# GMSL_SERIALIZER.net
KiCad netlist of a schematic drawn in Altium Designer
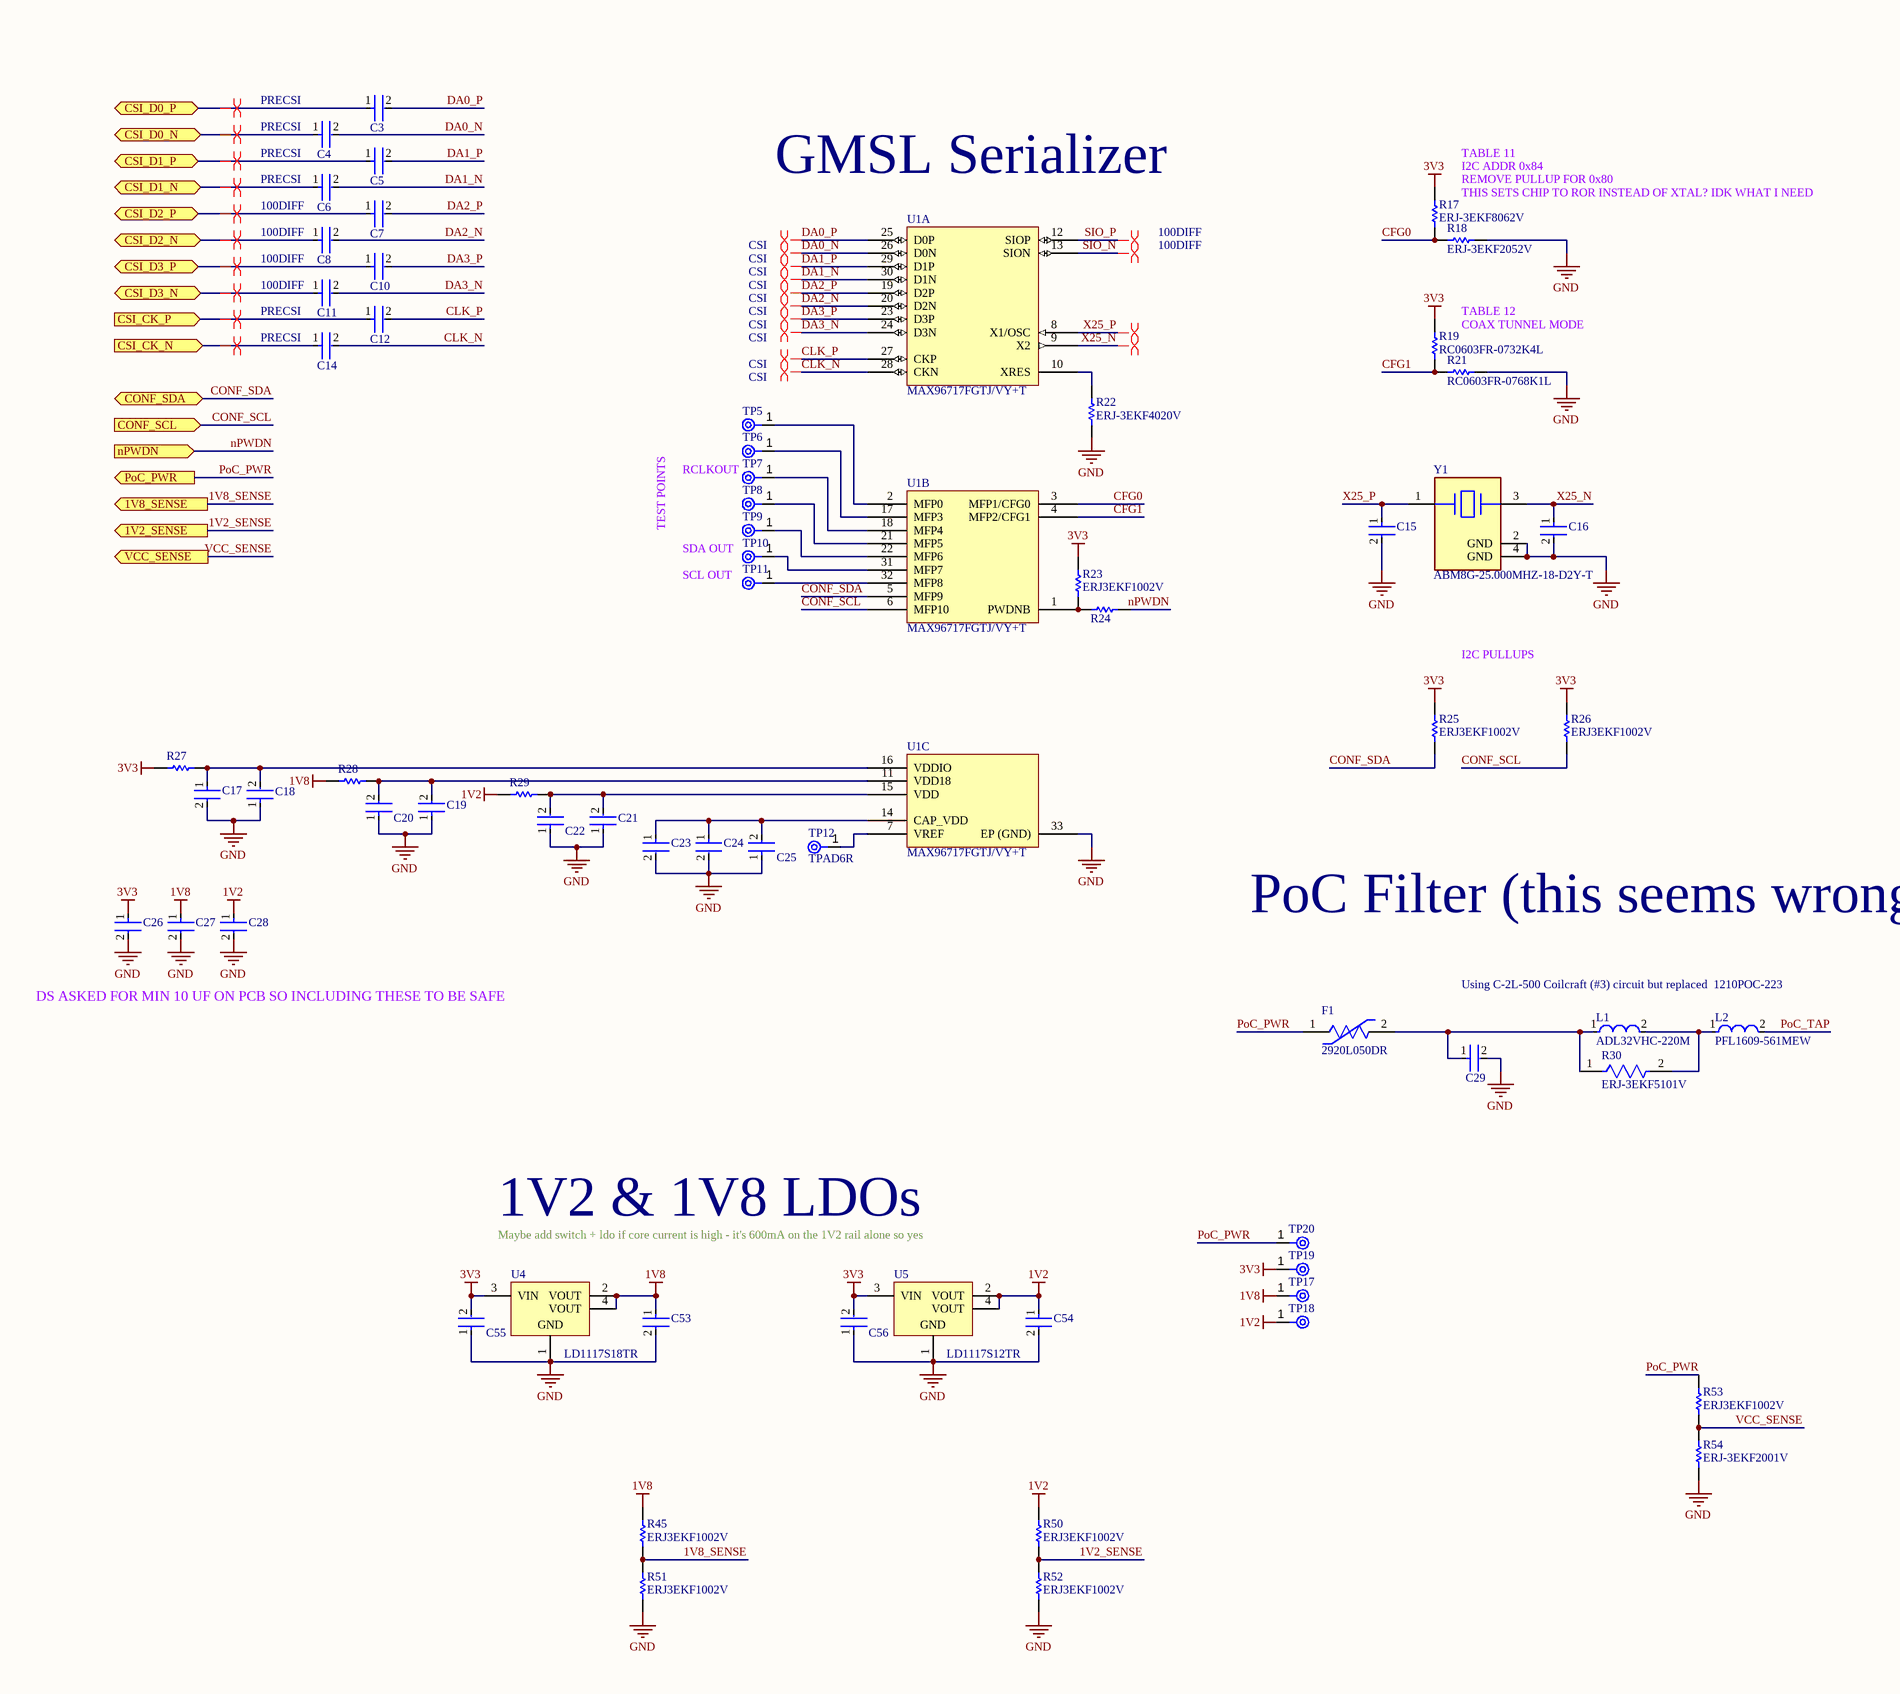
[diagram p0: GMSL_SERIALIZER.SchDoc, left]
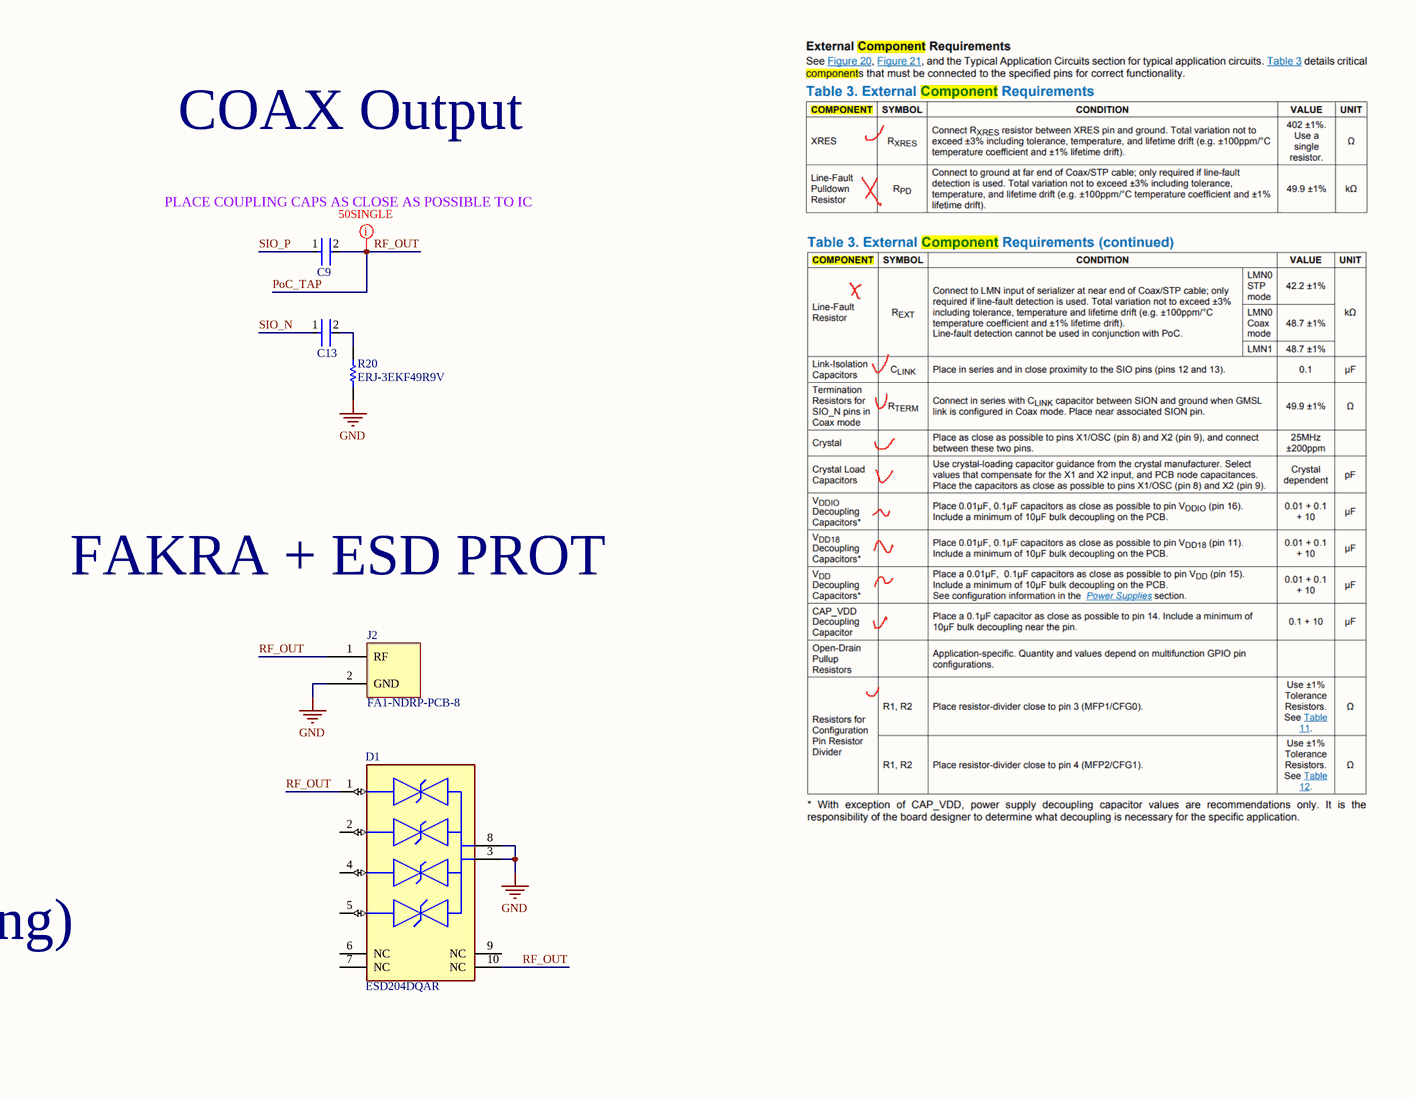
[diagram p1: GMSL_SERIALIZER.SchDoc, right]

(export (version "E")
  (design (tool "Eeschema 10.0.6"))
  (components
    (comp (ref "C3")
      (value "C1005X7R1H104K050BB")
      (footprint "FP-C1005-050-0_05-IPC_C")
      (description "Multilayer Ceramic Capacitors 100nF ±10% 50V X7R SMD 0402")
      (fields (field (name "VOLTAGE") "50V") (field (name "TOLERANCE") "10%"))
      (libsource (lib "Altium Content Vault") (part "b4654b650e69147ec39a6b967a45e02"))
    )
    (comp (ref "C4")
      (value "C1005X7R1H104K050BB")
      (footprint "FP-C1005-050-0_05-IPC_C")
      (description "Multilayer Ceramic Capacitors 100nF ±10% 50V X7R SMD 0402")
      (fields (field (name "VOLTAGE") "50V") (field (name "TOLERANCE") "10%"))
      (libsource (lib "Altium Content Vault") (part "b4654b650e69147ec39a6b967a45e02"))
    )
    (comp (ref "C5")
      (value "C1005X7R1H104K050BB")
      (footprint "FP-C1005-050-0_05-IPC_C")
      (description "Multilayer Ceramic Capacitors 100nF ±10% 50V X7R SMD 0402")
      (fields (field (name "VOLTAGE") "50V") (field (name "TOLERANCE") "10%"))
      (libsource (lib "Altium Content Vault") (part "b4654b650e69147ec39a6b967a45e02"))
    )
    (comp (ref "C6")
      (value "C1005X7R1H104K050BB")
      (footprint "FP-C1005-050-0_05-IPC_C")
      (description "Multilayer Ceramic Capacitors 100nF ±10% 50V X7R SMD 0402")
      (fields (field (name "VOLTAGE") "50V") (field (name "TOLERANCE") "10%"))
      (libsource (lib "Altium Content Vault") (part "b4654b650e69147ec39a6b967a45e02"))
    )
    (comp (ref "C7")
      (value "C1005X7R1H104K050BB")
      (footprint "FP-C1005-050-0_05-IPC_C")
      (description "Multilayer Ceramic Capacitors 100nF ±10% 50V X7R SMD 0402")
      (fields (field (name "VOLTAGE") "50V") (field (name "TOLERANCE") "10%"))
      (libsource (lib "Altium Content Vault") (part "b4654b650e69147ec39a6b967a45e02"))
    )
    (comp (ref "C8")
      (value "C1005X7R1H104K050BB")
      (footprint "FP-C1005-050-0_05-IPC_C")
      (description "Multilayer Ceramic Capacitors 100nF ±10% 50V X7R SMD 0402")
      (fields (field (name "VOLTAGE") "50V") (field (name "TOLERANCE") "10%"))
      (libsource (lib "Altium Content Vault") (part "b4654b650e69147ec39a6b967a45e02"))
    )
    (comp (ref "C9")
      (value "C1005X7R1H104K050BB")
      (footprint "FP-C1005-050-0_05-IPC_C")
      (description "Multilayer Ceramic Capacitors 100nF ±10% 50V X7R SMD 0402")
      (fields (field (name "VOLTAGE") "50V") (field (name "TOLERANCE") "10%"))
      (libsource (lib "Altium Content Vault") (part "b4654b650e69147ec39a6b967a45e02"))
    )
    (comp (ref "C10")
      (value "C1005X7R1H104K050BB")
      (footprint "FP-C1005-050-0_05-IPC_C")
      (description "Multilayer Ceramic Capacitors 100nF ±10% 50V X7R SMD 0402")
      (fields (field (name "VOLTAGE") "50V") (field (name "TOLERANCE") "10%"))
      (libsource (lib "Altium Content Vault") (part "b4654b650e69147ec39a6b967a45e02"))
    )
    (comp (ref "C11")
      (value "C1005X7R1H104K050BB")
      (footprint "FP-C1005-050-0_05-IPC_C")
      (description "Multilayer Ceramic Capacitors 100nF ±10% 50V X7R SMD 0402")
      (fields (field (name "VOLTAGE") "50V") (field (name "TOLERANCE") "10%"))
      (libsource (lib "Altium Content Vault") (part "b4654b650e69147ec39a6b967a45e02"))
    )
    (comp (ref "C12")
      (value "C1005X7R1H104K050BB")
      (footprint "FP-C1005-050-0_05-IPC_C")
      (description "Multilayer Ceramic Capacitors 100nF ±10% 50V X7R SMD 0402")
      (fields (field (name "VOLTAGE") "50V") (field (name "TOLERANCE") "10%"))
      (libsource (lib "Altium Content Vault") (part "b4654b650e69147ec39a6b967a45e02"))
    )
    (comp (ref "C13")
      (value "C1005X7R1H104K050BB")
      (footprint "FP-C1005-050-0_05-IPC_C")
      (description "Multilayer Ceramic Capacitors 100nF ±10% 50V X7R SMD 0402")
      (fields (field (name "VOLTAGE") "50V") (field (name "TOLERANCE") "10%"))
      (libsource (lib "Altium Content Vault") (part "b4654b650e69147ec39a6b967a45e02"))
    )
    (comp (ref "C14")
      (value "C1005X7R1H104K050BB")
      (footprint "FP-C1005-050-0_05-IPC_C")
      (description "Multilayer Ceramic Capacitors 100nF ±10% 50V X7R SMD 0402")
      (fields (field (name "VOLTAGE") "50V") (field (name "TOLERANCE") "10%"))
      (libsource (lib "Altium Content Vault") (part "b4654b650e69147ec39a6b967a45e02"))
    )
    (comp (ref "C15")
      (value "C0603C300J5GACTU")
      (footprint "FP-C0603C-CF-MFG")
      (description "CAP CER 30PF 50V 5% NP0 0603")
      (fields
        (field (name "MANUFACTURER") "KEMET")
        (field (name "OCTOPART") "https://octopart.com/c0603c300j5gactu-kemet-199455")
      )
      (libsource (lib "Altium Content Vault") (part "b4654b650e69147ec39a6b967a45e02"))
    )
    (comp (ref "C16")
      (value "C0603C300J5GACTU")
      (footprint "FP-C0603C-CF-MFG")
      (description "CAP CER 30PF 50V 5% NP0 0603")
      (fields
        (field (name "MANUFACTURER") "KEMET")
        (field (name "OCTOPART") "https://octopart.com/c0603c300j5gactu-kemet-199455")
      )
      (libsource (lib "Altium Content Vault") (part "b4654b650e69147ec39a6b967a45e02"))
    )
    (comp (ref "C17")
      (value "CL05A106MP5NUNC")
      (footprint "FP-CL05A106MP5NUNC-MFG")
      (description "CAP CER 10UF 10V X5R 0402")
      (fields
        (field (name "OCTOPART") "https://octopart.com/cl05a106mp5nunc-samsung-22457395")
        (field (name "TOLERANCE") "20%")
      )
      (libsource (lib "Altium Content Vault") (part "b4654b650e69147ec39a6b967a45e02"))
    )
    (comp (ref "C18")
      (value "C0402C103M5RACTU")
      (footprint "FP-C0402-BB-MFG")
      (description "CAP CER 10000PF 50V 20% X7R 0402")
      (fields
        (field (name "TOLERANCE") "0.2")
        (field (name "OCTOPART") "https://octopart.com/c0402c103m5ractu-kemet-17125571")
      )
      (libsource (lib "Altium Content Vault") (part "b4654b650e69147ec39a6b967a45e02"))
    )
    (comp (ref "C19")
      (value "C0402C103M5RACTU")
      (footprint "FP-C0402-BB-MFG")
      (description "CAP CER 10000PF 50V 20% X7R 0402")
      (fields
        (field (name "TOLERANCE") "0.2")
        (field (name "OCTOPART") "https://octopart.com/c0402c103m5ractu-kemet-17125571")
      )
      (libsource (lib "Altium Content Vault") (part "b4654b650e69147ec39a6b967a45e02"))
    )
    (comp (ref "C20")
      (value "C1005X7R1H104K050BB")
      (footprint "FP-C1005-050-0_05-IPC_C")
      (description "Multilayer Ceramic Capacitors 100nF ±10% 50V X7R SMD 0402")
      (fields (field (name "VOLTAGE") "50V") (field (name "TOLERANCE") "10%"))
      (libsource (lib "Altium Content Vault") (part "b4654b650e69147ec39a6b967a45e02"))
    )
    (comp (ref "C21")
      (value "C0402C103M5RACTU")
      (footprint "FP-C0402-BB-MFG")
      (description "CAP CER 10000PF 50V 20% X7R 0402")
      (fields
        (field (name "TOLERANCE") "0.2")
        (field (name "OCTOPART") "https://octopart.com/c0402c103m5ractu-kemet-17125571")
      )
      (libsource (lib "Altium Content Vault") (part "b4654b650e69147ec39a6b967a45e02"))
    )
    (comp (ref "C22")
      (value "C1005X7R1H104K050BB")
      (footprint "FP-C1005-050-0_05-IPC_C")
      (description "Multilayer Ceramic Capacitors 100nF ±10% 50V X7R SMD 0402")
      (fields (field (name "VOLTAGE") "50V") (field (name "TOLERANCE") "10%"))
      (libsource (lib "Altium Content Vault") (part "b4654b650e69147ec39a6b967a45e02"))
    )
    (comp (ref "C23")
      (value "CL05A106MP5NUNC")
      (footprint "FP-CL05A106MP5NUNC-MFG")
      (description "CAP CER 10UF 10V X5R 0402")
      (fields
        (field (name "OCTOPART") "https://octopart.com/cl05a106mp5nunc-samsung-22457395")
        (field (name "TOLERANCE") "20%")
      )
      (libsource (lib "Altium Content Vault") (part "b4654b650e69147ec39a6b967a45e02"))
    )
    (comp (ref "C24")
      (value "CL05A106MP5NUNC")
      (footprint "FP-CL05A106MP5NUNC-MFG")
      (description "CAP CER 10UF 10V X5R 0402")
      (fields
        (field (name "OCTOPART") "https://octopart.com/cl05a106mp5nunc-samsung-22457395")
        (field (name "TOLERANCE") "20%")
      )
      (libsource (lib "Altium Content Vault") (part "b4654b650e69147ec39a6b967a45e02"))
    )
    (comp (ref "C25")
      (value "C1005X7R1H104K050BB")
      (footprint "FP-C1005-050-0_05-IPC_C")
      (description "Multilayer Ceramic Capacitors 100nF ±10% 50V X7R SMD 0402")
      (fields (field (name "VOLTAGE") "50V") (field (name "TOLERANCE") "10%"))
      (libsource (lib "Altium Content Vault") (part "b4654b650e69147ec39a6b967a45e02"))
    )
    (comp (ref "C26")
      (value "CL05A106MP5NUNC")
      (footprint "FP-CL05A106MP5NUNC-MFG")
      (description "CAP CER 10UF 10V X5R 0402")
      (fields
        (field (name "OCTOPART") "https://octopart.com/cl05a106mp5nunc-samsung-22457395")
        (field (name "TOLERANCE") "20%")
      )
      (libsource (lib "Altium Content Vault") (part "b4654b650e69147ec39a6b967a45e02"))
    )
    (comp (ref "C27")
      (value "CL05A106MP5NUNC")
      (footprint "FP-CL05A106MP5NUNC-MFG")
      (description "CAP CER 10UF 10V X5R 0402")
      (fields
        (field (name "OCTOPART") "https://octopart.com/cl05a106mp5nunc-samsung-22457395")
        (field (name "TOLERANCE") "20%")
      )
      (libsource (lib "Altium Content Vault") (part "b4654b650e69147ec39a6b967a45e02"))
    )
    (comp (ref "C28")
      (value "CL05A106MP5NUNC")
      (footprint "FP-CL05A106MP5NUNC-MFG")
      (description "CAP CER 10UF 10V X5R 0402")
      (fields
        (field (name "OCTOPART") "https://octopart.com/cl05a106mp5nunc-samsung-22457395")
        (field (name "TOLERANCE") "20%")
      )
      (libsource (lib "Altium Content Vault") (part "b4654b650e69147ec39a6b967a45e02"))
    )
    (comp (ref "C29")
      (value "GRM21BR61E226ME44L")
      (footprint "FP-GRM21B-0_2-e0_2_0_7-IPC_B")
      (description "Chip Multilayer Ceramic Capacitors for General Purpose, 0805, 22uF, X5R, 15%, 20%, 25V")
      (fields (field (name "TOLERANCE") "20%") (field (name "VOLTAGE") "25V"))
      (libsource (lib "Altium Content Vault") (part "b4654b650e69147ec39a6b967a45e02"))
    )
    (comp (ref "C53")
      (value "GRM188R60J106ME47D")
      (footprint "FP-GRM188-0_1-e0_2_0_55-IPC_A")
      (description "Chip Multilayer Ceramic Capacitors for General Purpose, 0603, 10uF, X5R, 15%, 20%, 6.3V")
      (fields (field (name "VOLTAGE") "6.3V") (field (name "TOLERANCE") "20%"))
      (libsource (lib "Altium Content Vault") (part "02cd4be3c70576c341d710602a673aa"))
    )
    (comp (ref "C54")
      (value "GRM188R60J106ME47D")
      (footprint "FP-GRM188-0_1-e0_2_0_55-IPC_A")
      (description "Chip Multilayer Ceramic Capacitors for General Purpose, 0603, 10uF, X5R, 15%, 20%, 6.3V")
      (fields (field (name "VOLTAGE") "6.3V") (field (name "TOLERANCE") "20%"))
      (libsource (lib "Altium Content Vault") (part "02cd4be3c70576c341d710602a673aa"))
    )
    (comp (ref "C55")
      (value "C1005X7R1H104K050BB")
      (footprint "FP-C1005-050-0_05-IPC_C")
      (description "Multilayer Ceramic Capacitors 100nF ±10% 50V X7R SMD 0402")
      (fields (field (name "VOLTAGE") "50V") (field (name "TOLERANCE") "10%"))
      (libsource (lib "Altium Content Vault") (part "b4654b650e69147ec39a6b967a45e02"))
    )
    (comp (ref "C56")
      (value "C1005X7R1H104K050BB")
      (footprint "FP-C1005-050-0_05-IPC_C")
      (description "Multilayer Ceramic Capacitors 100nF ±10% 50V X7R SMD 0402")
      (fields (field (name "VOLTAGE") "50V") (field (name "TOLERANCE") "10%"))
      (libsource (lib "Altium Content Vault") (part "b4654b650e69147ec39a6b967a45e02"))
    )
    (comp (ref "D1")
      (value "ESD204DQAR")
      (footprint "FP-DQA0010A-MFG")
      (description "4-CHANNEL LOW-CAPACITANCE SURGE")
      (fields
        (field (name "MANUFACTURER") "Texas Instruments")
        (field (name "OCTOPART") "https://octopart.com/esd204dqar-texas+instruments-89917476")
      )
      (libsource (lib "Altium Content Vault") (part "1465e58c1818c7767b55926832f0bf5"))
    )
    (comp (ref "F1")
      (value "2920L050DR")
      (footprint "FP-2920L050DR-MFG")
      (description "PTC RESET FUSE 60V 500MA 2920")
      (libsource (lib "Altium Content Vault") (part "1c6d77a0208143737455a0c7eb396be"))
    )
    (comp (ref "J2")
      (value "FA1-NDRP-PCB-8")
      (footprint "FA1-NDRP-PCB-8-Footprint-1")
      (description "RF F Connector, Male, Board Mount, Solder Terminal, Plug")
      (libsource (lib "Space Concordia") (part "FA1-NDRP-PCB-8"))
    )
    (comp (ref "L1")
      (value "ADL32VHC-220M")
      (footprint "FP-1210POC-MFG")
      (description "NOT COILCRAFT - ACTUAL P# --> ADL32VHC-220M\r\n - Power Injection Chokes for PoC")
      (fields
        (field (name "MANUFACTURER") "coilcraft")
        (field (name "OCTOPART") "https://octopart.com/1210poc-223mrc-coilcraft-103207315")
      )
      (libsource (lib "Altium Content Vault") (part "725321dda6339637d4d059423bc1c3c"))
    )
    (comp (ref "L2")
      (value "PFL1609-561MEW")
      (footprint "FP-PFL1609-MFG")
      (description "Fixed Inductors PFL1609 Low Profile 0.56 uH 20 % 1.4 A")
      (fields (field (name "MANUFACTURER") "coilcraft") (field (name "TOLERANCE") "20%"))
      (libsource (lib "Altium Content Vault") (part "725321dda6339637d4d059423bc1c3c"))
    )
    (comp (ref "R17")
      (value "ERJ-3EKF8062V")
      (footprint "RESC1608X55X30LL15T15")
      (fields (field (name "MANUFACTURER") "Panasonic"))
      (libsource (lib "Altium Content Vault") (part "RES"))
    )
    (comp (ref "R18")
      (value "ERJ-3EKF2052V")
      (footprint "RESC1608X55X30NL15T15")
      (fields (field (name "MANUFACTURER") "Panasonic"))
      (libsource (lib "Altium Content Vault") (part "RES"))
    )
    (comp (ref "R19")
      (value "RC0603FR-0732K4L")
      (footprint "RESC1608X55X25ML10T15")
      (fields (field (name "MANUFACTURER") "Yageo"))
      (libsource (lib "Altium Content Vault") (part "RES"))
    )
    (comp (ref "R20")
      (value "ERJ-3EKF49R9V")
      (footprint "RESC1608X55X30ML15T15")
      (fields (field (name "MANUFACTURER") "Panasonic"))
      (libsource (lib "Altium Content Vault") (part "RES"))
    )
    (comp (ref "R21")
      (value "RC0603FR-0768K1L")
      (footprint "RESC1608X55X25LL10T15")
      (fields (field (name "MANUFACTURER") "Yageo"))
      (libsource (lib "Altium Content Vault") (part "RES"))
    )
    (comp (ref "R22")
      (value "ERJ-3EKF4020V")
      (footprint "RESC1608X55X30LL15T15")
      (fields (field (name "MANUFACTURER") "Panasonic"))
      (libsource (lib "Altium Content Vault") (part "RES"))
    )
    (comp (ref "R23")
      (value "ERJ3EKF1002V")
      (footprint "RESC1609X55X30LL15T15")
      (description "Chip Resistor, 10 KOhm, +/- 1%, 0.1 W, -55 to 155 degC, 0603 (1608 Metric), RoHS, Tape and Reel")
      (fields (field (name "TOLERANCE") "1%") (field (name "MANUFACTURER") "Panasonic"))
      (libsource (lib "Altium Content Vault") (part "RES-2"))
    )
    (comp (ref "R24")
      (value "0402 JUMPER")
      (footprint "RESC1005X40X25ML05T05")
      (description "READ THE NAME")
      (libsource (lib "Space Concordia") (part "CMP-009-00206-2"))
    )
    (comp (ref "R25")
      (value "ERJ3EKF1002V")
      (footprint "RESC1609X55X30LL15T15")
      (description "Chip Resistor, 10 KOhm, +/- 1%, 0.1 W, -55 to 155 degC, 0603 (1608 Metric), RoHS, Tape and Reel")
      (fields (field (name "TOLERANCE") "1%") (field (name "MANUFACTURER") "Panasonic"))
      (libsource (lib "Altium Content Vault") (part "RES-2"))
    )
    (comp (ref "R26")
      (value "ERJ3EKF1002V")
      (footprint "RESC1609X55X30LL15T15")
      (description "Chip Resistor, 10 KOhm, +/- 1%, 0.1 W, -55 to 155 degC, 0603 (1608 Metric), RoHS, Tape and Reel")
      (fields (field (name "TOLERANCE") "1%") (field (name "MANUFACTURER") "Panasonic"))
      (libsource (lib "Altium Content Vault") (part "RES-2"))
    )
    (comp (ref "R27")
      (value "RC0402JR-070RL")
      (footprint "RESC1005X40X25NL05T10")
      (fields (field (name "MANUFACTURER") "Yageo / Phycomp"))
      (libsource (lib "Altium Content Vault") (part "RES"))
    )
    (comp (ref "R28")
      (value "RC0402JR-070RL")
      (footprint "RESC1005X40X25NL05T10")
      (fields (field (name "MANUFACTURER") "Yageo / Phycomp"))
      (libsource (lib "Altium Content Vault") (part "RES"))
    )
    (comp (ref "R29")
      (value "RC0402JR-070RL")
      (footprint "RESC1005X40X25NL05T10")
      (fields (field (name "MANUFACTURER") "Yageo / Phycomp"))
      (libsource (lib "Altium Content Vault") (part "RES"))
    )
    (comp (ref "R30")
      (value "ERJ-3EKF5101V")
      (footprint "FP-ERJ3EK-MFG")
      (description "RES SMD 5.1K OHM 1% 1/10W 0603")
      (fields (field (name "TOLERANCE") "1%"))
      (libsource (lib "Altium Content Vault") (part "1029c3af85768c4190bb7ad29bc67b5"))
    )
    (comp (ref "R45")
      (value "ERJ3EKF1002V")
      (footprint "RESC1609X55X30LL15T15")
      (description "Chip Resistor, 10 KOhm, +/- 1%, 0.1 W, -55 to 155 degC, 0603 (1608 Metric), RoHS, Tape and Reel")
      (fields (field (name "TOLERANCE") "1%") (field (name "MANUFACTURER") "Panasonic"))
      (libsource (lib "Altium Content Vault") (part "RES-2"))
    )
    (comp (ref "R50")
      (value "ERJ3EKF1002V")
      (footprint "RESC1609X55X30LL15T15")
      (description "Chip Resistor, 10 KOhm, +/- 1%, 0.1 W, -55 to 155 degC, 0603 (1608 Metric), RoHS, Tape and Reel")
      (fields (field (name "TOLERANCE") "1%") (field (name "MANUFACTURER") "Panasonic"))
      (libsource (lib "Altium Content Vault") (part "RES-2"))
    )
    (comp (ref "R51")
      (value "ERJ3EKF1002V")
      (footprint "RESC1609X55X30LL15T15")
      (description "Chip Resistor, 10 KOhm, +/- 1%, 0.1 W, -55 to 155 degC, 0603 (1608 Metric), RoHS, Tape and Reel")
      (fields (field (name "TOLERANCE") "1%") (field (name "MANUFACTURER") "Panasonic"))
      (libsource (lib "Altium Content Vault") (part "RES-2"))
    )
    (comp (ref "R52")
      (value "ERJ3EKF1002V")
      (footprint "RESC1609X55X30LL15T15")
      (description "Chip Resistor, 10 KOhm, +/- 1%, 0.1 W, -55 to 155 degC, 0603 (1608 Metric), RoHS, Tape and Reel")
      (fields (field (name "TOLERANCE") "1%") (field (name "MANUFACTURER") "Panasonic"))
      (libsource (lib "Altium Content Vault") (part "RES-2"))
    )
    (comp (ref "R53")
      (value "ERJ3EKF1002V")
      (footprint "RESC1609X55X30LL15T15")
      (description "Chip Resistor, 10 KOhm, +/- 1%, 0.1 W, -55 to 155 degC, 0603 (1608 Metric), RoHS, Tape and Reel")
      (fields (field (name "TOLERANCE") "1%") (field (name "MANUFACTURER") "Panasonic"))
      (libsource (lib "Altium Content Vault") (part "RES-2"))
    )
    (comp (ref "R54")
      (value "ERJ-3EKF2001V")
      (footprint "RESC1608X55X30ML15T15")
      (fields (field (name "MANUFACTURER") "Panasonic"))
      (libsource (lib "Altium Content Vault") (part "RES"))
    )
    (comp (ref "TP5")
      (value "TPAD6R")
      (footprint "New footprint 1")
      (description "Test Point .6mm")
      (libsource (lib "Space Concordia") (part "TP"))
    )
    (comp (ref "TP6")
      (value "TPAD6R")
      (footprint "New footprint 1")
      (description "Test Point .6mm")
      (libsource (lib "Space Concordia") (part "TP"))
    )
    (comp (ref "TP7")
      (value "TPAD6R")
      (footprint "New footprint 1")
      (description "Test Point .6mm")
      (libsource (lib "Space Concordia") (part "TP"))
    )
    (comp (ref "TP8")
      (value "TPAD6R")
      (footprint "New footprint 1")
      (description "Test Point .6mm")
      (libsource (lib "Space Concordia") (part "TP"))
    )
    (comp (ref "TP9")
      (value "TPAD6R")
      (footprint "New footprint 1")
      (description "Test Point .6mm")
      (libsource (lib "Space Concordia") (part "TP"))
    )
    (comp (ref "TP10")
      (value "TPAD6R")
      (footprint "New footprint 1")
      (description "Test Point .6mm")
      (libsource (lib "Space Concordia") (part "TP"))
    )
    (comp (ref "TP11")
      (value "TPAD6R")
      (footprint "New footprint 1")
      (description "Test Point .6mm")
      (libsource (lib "Space Concordia") (part "TP"))
    )
    (comp (ref "TP12")
      (value "TPAD6R")
      (footprint "New footprint 1")
      (description "Test Point .6mm")
      (libsource (lib "Space Concordia") (part "TP"))
    )
    (comp (ref "TP17")
      (value "TPAD6R")
      (footprint "New footprint 1")
      (description "Test Point .6mm")
      (libsource (lib "Space Concordia") (part "TP"))
    )
    (comp (ref "TP18")
      (value "TPAD6R")
      (footprint "New footprint 1")
      (description "Test Point .6mm")
      (libsource (lib "Space Concordia") (part "TP"))
    )
    (comp (ref "TP19")
      (value "TPAD6R")
      (footprint "New footprint 1")
      (description "Test Point .6mm")
      (libsource (lib "Space Concordia") (part "TP"))
    )
    (comp (ref "TP20")
      (value "TPAD6R")
      (footprint "New footprint 1")
      (description "Test Point .6mm")
      (libsource (lib "Space Concordia") (part "TP"))
    )
    (comp (ref "U1")
      (value "MAX96717FGTJ/VY+T")
      (footprint "QFN50P500X500X80_HS-33N")
      (description "3Gbps Serializer TQFN-32 Serializers / Deserializers ROHS")
      (libsource (lib "Space Concordia") (part "MAX96717FGTJ_VY+T"))
    )
    (comp (ref "U4")
      (value "LD1117S18TR")
      (footprint "SOT-223_M")
      (description "Fixed Low Drop Positive Voltage Regulator, 1.8V, 4-Pin SOT-223, Tape and Reel")
      (libsource (lib "Altium Content Vault") (part "PM-REG-LD1117-SOT4"))
    )
    (comp (ref "U5")
      (value "LD1117S12TR")
      (footprint "SOT-223_M")
      (description "Fixed Low Drop Positive Voltage Regulator, 1.2V, 4-Pin SOT-223, Tape and Reel")
      (libsource (lib "Altium Content Vault") (part "PM-REG-LD1117-SOT4"))
    )
    (comp (ref "Y1")
      (value "ABM8G-25.000MHZ-18-D2Y-T")
      (footprint "FP-ABM8G-MFG")
      (description "Crystal 25MHz ±20ppm (Tol) ±30ppm (Stability) 18pF FUND 60Ω 4-Pin SMD T/R")
      (fields (field (name "TOLERANCE") "20ppm"))
      (libsource (lib "Altium Content Vault") (part "48e526d86b7f2615d98721063c72f49"))
    )
  )
  (nets
    (net (code "1") (name "/1V2_SENSE") (class "Default")
      (node (ref "R50") (pin "1") (pinfunction "1_1") (pintype "passive"))
      (node (ref "R52") (pin "2") (pinfunction "2_2") (pintype "passive"))
    )
    (net (code "2") (name "/1V8_SENSE") (class "Default")
      (node (ref "R45") (pin "1") (pinfunction "1_1") (pintype "passive"))
      (node (ref "R51") (pin "2") (pinfunction "2_2") (pintype "passive"))
    )
    (net (code "3") (name "/CFG0") (class "Default")
      (node (ref "R17") (pin "1") (pinfunction "1_1") (pintype "passive"))
      (node (ref "R18") (pin "2") (pinfunction "2_2") (pintype "passive"))
      (node (ref "U1") (pin "3") (pinfunction "MFP1/CFG0_3") (pintype "passive"))
    )
    (net (code "4") (name "/CFG1") (class "Default")
      (node (ref "R19") (pin "1") (pinfunction "1_1") (pintype "passive"))
      (node (ref "R21") (pin "2") (pinfunction "2_2") (pintype "passive"))
      (node (ref "U1") (pin "4") (pinfunction "MFP2/CFG1_4") (pintype "passive"))
    )
    (net (code "5") (name "/CLK_N") (class "Default")
      (node (ref "C14") (pin "2") (pinfunction "2_2") (pintype "passive"))
      (node (ref "U1") (pin "28") (pinfunction "CKN_28") (pintype "bidirectional"))
    )
    (net (code "6") (name "/CLK_P") (class "Default")
      (node (ref "C12") (pin "2") (pinfunction "2_2") (pintype "passive"))
      (node (ref "U1") (pin "27") (pinfunction "CKP_27") (pintype "bidirectional"))
    )
    (net (code "7") (name "/CONF_SCL") (class "Default")
      (node (ref "R26") (pin "1") (pinfunction "1_1") (pintype "passive"))
      (node (ref "U1") (pin "6") (pinfunction "MFP10_6") (pintype "passive"))
    )
    (net (code "8") (name "/CONF_SDA") (class "Default")
      (node (ref "R25") (pin "1") (pinfunction "1_1") (pintype "passive"))
      (node (ref "U1") (pin "5") (pinfunction "MFP9_5") (pintype "passive"))
    )
    (net (code "9") (name "/CSI_CK_N") (class "Default")
      (node (ref "C14") (pin "1") (pinfunction "1_1") (pintype "passive"))
    )
    (net (code "10") (name "/CSI_CK_P") (class "Default")
      (node (ref "C12") (pin "1") (pinfunction "1_1") (pintype "passive"))
    )
    (net (code "11") (name "/CSI_D0_N") (class "Default")
      (node (ref "C4") (pin "1") (pinfunction "1_1") (pintype "passive"))
    )
    (net (code "12") (name "/CSI_D0_P") (class "Default")
      (node (ref "C3") (pin "1") (pinfunction "1_1") (pintype "passive"))
    )
    (net (code "13") (name "/CSI_D1_N") (class "Default")
      (node (ref "C6") (pin "1") (pinfunction "1_1") (pintype "passive"))
    )
    (net (code "14") (name "/CSI_D1_P") (class "Default")
      (node (ref "C5") (pin "1") (pinfunction "1_1") (pintype "passive"))
    )
    (net (code "15") (name "/CSI_D2_N") (class "Default")
      (node (ref "C8") (pin "1") (pinfunction "1_1") (pintype "passive"))
    )
    (net (code "16") (name "/CSI_D2_P") (class "Default")
      (node (ref "C7") (pin "1") (pinfunction "1_1") (pintype "passive"))
    )
    (net (code "17") (name "/CSI_D3_N") (class "Default")
      (node (ref "C11") (pin "1") (pinfunction "1_1") (pintype "passive"))
    )
    (net (code "18") (name "/CSI_D3_P") (class "Default")
      (node (ref "C10") (pin "1") (pinfunction "1_1") (pintype "passive"))
    )
    (net (code "19") (name "/DA0_N") (class "Default")
      (node (ref "C4") (pin "2") (pinfunction "2_2") (pintype "passive"))
      (node (ref "U1") (pin "26") (pinfunction "D0N_26") (pintype "bidirectional"))
    )
    (net (code "20") (name "/DA0_P") (class "Default")
      (node (ref "C3") (pin "2") (pinfunction "2_2") (pintype "passive"))
      (node (ref "U1") (pin "25") (pinfunction "D0P_25") (pintype "bidirectional"))
    )
    (net (code "21") (name "/DA1_N") (class "Default")
      (node (ref "C6") (pin "2") (pinfunction "2_2") (pintype "passive"))
      (node (ref "U1") (pin "30") (pinfunction "D1N_30") (pintype "bidirectional"))
    )
    (net (code "22") (name "/DA1_P") (class "Default")
      (node (ref "C5") (pin "2") (pinfunction "2_2") (pintype "passive"))
      (node (ref "U1") (pin "29") (pinfunction "D1P_29") (pintype "bidirectional"))
    )
    (net (code "23") (name "/DA2_N") (class "Default")
      (node (ref "C8") (pin "2") (pinfunction "2_2") (pintype "passive"))
      (node (ref "U1") (pin "20") (pinfunction "D2N_20") (pintype "bidirectional"))
    )
    (net (code "24") (name "/DA2_P") (class "Default")
      (node (ref "C7") (pin "2") (pinfunction "2_2") (pintype "passive"))
      (node (ref "U1") (pin "19") (pinfunction "D2P_19") (pintype "bidirectional"))
    )
    (net (code "25") (name "/DA3_N") (class "Default")
      (node (ref "C11") (pin "2") (pinfunction "2_2") (pintype "passive"))
      (node (ref "U1") (pin "24") (pinfunction "D3N_24") (pintype "bidirectional"))
    )
    (net (code "26") (name "/DA3_P") (class "Default")
      (node (ref "C10") (pin "2") (pinfunction "2_2") (pintype "passive"))
      (node (ref "U1") (pin "23") (pinfunction "D3P_23") (pintype "bidirectional"))
    )
    (net (code "27") (name "/PoC_PWR") (class "Default")
      (node (ref "F1") (pin "1") (pinfunction "1_1") (pintype "passive"))
      (node (ref "R53") (pin "2") (pinfunction "2_2") (pintype "passive"))
      (node (ref "TP20") (pin "1") (pinfunction "TP_1") (pintype "passive"))
    )
    (net (code "28") (name "/PoC_TAP") (class "Default")
      (node (ref "C9") (pin "2") (pinfunction "2_2") (pintype "passive"))
      (node (ref "D1") (pin "1") (pinfunction "IO1_1") (pintype "bidirectional"))
      (node (ref "D1") (pin "10") (pinfunction "NC_10") (pintype "passive"))
      (node (ref "J2") (pin "1") (pinfunction "RF_1") (pintype "passive"))
      (node (ref "L2") (pin "2") (pinfunction "2_2") (pintype "passive"))
    )
    (net (code "29") (name "/SIO_N") (class "Default")
      (node (ref "C13") (pin "1") (pinfunction "1_1") (pintype "passive"))
      (node (ref "U1") (pin "13") (pinfunction "SION_13") (pintype "bidirectional"))
    )
    (net (code "30") (name "/SIO_P") (class "Default")
      (node (ref "C9") (pin "1") (pinfunction "1_1") (pintype "passive"))
      (node (ref "U1") (pin "12") (pinfunction "SIOP_12") (pintype "bidirectional"))
    )
    (net (code "31") (name "/VCC_SENSE") (class "Default")
      (node (ref "R53") (pin "1") (pinfunction "1_1") (pintype "passive"))
      (node (ref "R54") (pin "2") (pinfunction "2_2") (pintype "passive"))
    )
    (net (code "32") (name "/X25_N") (class "Default")
      (node (ref "C16") (pin "1") (pinfunction "1_1") (pintype "passive"))
      (node (ref "U1") (pin "9") (pinfunction "X2_9") (pintype "output"))
      (node (ref "Y1") (pin "3") (pinfunction "3_3") (pintype "passive"))
    )
    (net (code "33") (name "/X25_P") (class "Default")
      (node (ref "C15") (pin "1") (pinfunction "1_1") (pintype "passive"))
      (node (ref "U1") (pin "8") (pinfunction "X1/OSC_8") (pintype "input"))
      (node (ref "Y1") (pin "1") (pinfunction "1_1") (pintype "passive"))
    )
    (net (code "34") (name "/nPWDN") (class "Default")
      (node (ref "R24") (pin "2") (pinfunction "2_2") (pintype "passive"))
    )
    (net (code "35") (name "1V2") (class "Default")
      (node (ref "C28") (pin "1") (pinfunction "1_1") (pintype "passive"))
      (node (ref "C54") (pin "1") (pinfunction "1_1") (pintype "passive"))
      (node (ref "R29") (pin "1") (pinfunction "1_1") (pintype "passive"))
      (node (ref "R50") (pin "2") (pinfunction "2_2") (pintype "passive"))
      (node (ref "TP18") (pin "1") (pinfunction "TP_1") (pintype "passive"))
      (node (ref "U5") (pin "2") (pinfunction "VOUT_2") (pintype "power_in"))
      (node (ref "U5") (pin "4") (pinfunction "VOUT_4") (pintype "power_in"))
    )
    (net (code "36") (name "1V8") (class "Default")
      (node (ref "C27") (pin "1") (pinfunction "1_1") (pintype "passive"))
      (node (ref "C53") (pin "1") (pinfunction "1_1") (pintype "passive"))
      (node (ref "R28") (pin "1") (pinfunction "1_1") (pintype "passive"))
      (node (ref "R45") (pin "2") (pinfunction "2_2") (pintype "passive"))
      (node (ref "TP17") (pin "1") (pinfunction "TP_1") (pintype "passive"))
      (node (ref "U4") (pin "2") (pinfunction "VOUT_2") (pintype "power_in"))
      (node (ref "U4") (pin "4") (pinfunction "VOUT_4") (pintype "power_in"))
    )
    (net (code "37") (name "3V3") (class "Default")
      (node (ref "C26") (pin "1") (pinfunction "1_1") (pintype "passive"))
      (node (ref "C55") (pin "2") (pinfunction "2_2") (pintype "passive"))
      (node (ref "C56") (pin "2") (pinfunction "2_2") (pintype "passive"))
      (node (ref "R17") (pin "2") (pinfunction "2_2") (pintype "passive"))
      (node (ref "R19") (pin "2") (pinfunction "2_2") (pintype "passive"))
      (node (ref "R23") (pin "2") (pinfunction "2_2") (pintype "passive"))
      (node (ref "R25") (pin "2") (pinfunction "2_2") (pintype "passive"))
      (node (ref "R26") (pin "2") (pinfunction "2_2") (pintype "passive"))
      (node (ref "R27") (pin "1") (pinfunction "1_1") (pintype "passive"))
      (node (ref "TP19") (pin "1") (pinfunction "TP_1") (pintype "passive"))
      (node (ref "U4") (pin "3") (pinfunction "VIN_3") (pintype "power_in"))
      (node (ref "U5") (pin "3") (pinfunction "VIN_3") (pintype "power_in"))
    )
    (net (code "38") (name "GND") (class "Default")
      (node (ref "C15") (pin "2") (pinfunction "2_2") (pintype "passive"))
      (node (ref "C16") (pin "2") (pinfunction "2_2") (pintype "passive"))
      (node (ref "C17") (pin "2") (pinfunction "2_2") (pintype "passive"))
      (node (ref "C18") (pin "1") (pinfunction "1_1") (pintype "passive"))
      (node (ref "C19") (pin "1") (pinfunction "1_1") (pintype "passive"))
      (node (ref "C20") (pin "1") (pinfunction "1_1") (pintype "passive"))
      (node (ref "C21") (pin "1") (pinfunction "1_1") (pintype "passive"))
      (node (ref "C22") (pin "1") (pinfunction "1_1") (pintype "passive"))
      (node (ref "C23") (pin "2") (pinfunction "2_2") (pintype "passive"))
      (node (ref "C24") (pin "2") (pinfunction "2_2") (pintype "passive"))
      (node (ref "C25") (pin "1") (pinfunction "1_1") (pintype "passive"))
      (node (ref "C26") (pin "2") (pinfunction "2_2") (pintype "passive"))
      (node (ref "C27") (pin "2") (pinfunction "2_2") (pintype "passive"))
      (node (ref "C28") (pin "2") (pinfunction "2_2") (pintype "passive"))
      (node (ref "C29") (pin "2") (pinfunction "2_2") (pintype "passive"))
      (node (ref "C53") (pin "2") (pinfunction "2_2") (pintype "passive"))
      (node (ref "C54") (pin "2") (pinfunction "2_2") (pintype "passive"))
      (node (ref "C55") (pin "1") (pinfunction "1_1") (pintype "passive"))
      (node (ref "C56") (pin "1") (pinfunction "1_1") (pintype "passive"))
      (node (ref "D1") (pin "3") (pinfunction "GND_3") (pintype "power_in"))
      (node (ref "D1") (pin "8") (pinfunction "GND_8") (pintype "power_in"))
      (node (ref "J2") (pin "2") (pinfunction "GND_2") (pintype "passive"))
      (node (ref "R18") (pin "1") (pinfunction "1_1") (pintype "passive"))
      (node (ref "R20") (pin "1") (pinfunction "1_1") (pintype "passive"))
      (node (ref "R21") (pin "1") (pinfunction "1_1") (pintype "passive"))
      (node (ref "R22") (pin "1") (pinfunction "1_1") (pintype "passive"))
      (node (ref "R51") (pin "1") (pinfunction "1_1") (pintype "passive"))
      (node (ref "R52") (pin "1") (pinfunction "1_1") (pintype "passive"))
      (node (ref "R54") (pin "1") (pinfunction "1_1") (pintype "passive"))
      (node (ref "U1") (pin "33") (pinfunction "EP_(GND)_33") (pintype "power_in"))
      (node (ref "U4") (pin "1") (pinfunction "GND_1") (pintype "power_in"))
      (node (ref "U5") (pin "1") (pinfunction "GND_1") (pintype "power_in"))
      (node (ref "Y1") (pin "2") (pinfunction "GND_2") (pintype "power_in"))
      (node (ref "Y1") (pin "4") (pinfunction "GND_4") (pintype "power_in"))
    )
    (net (code "39") (name "Net-(C13-Pad2)") (class "Default")
      (node (ref "C13") (pin "2") (pinfunction "2_2") (pintype "passive"))
      (node (ref "R20") (pin "2") (pinfunction "2_2") (pintype "passive"))
    )
    (net (code "40") (name "Net-(C29-Pad1)") (class "Default")
      (node (ref "C29") (pin "1") (pinfunction "1_1") (pintype "passive"))
      (node (ref "F1") (pin "2") (pinfunction "2_2") (pintype "passive"))
      (node (ref "L1") (pin "1") (pinfunction "1_1") (pintype "passive"))
      (node (ref "R30") (pin "1") (pinfunction "1_1") (pintype "passive"))
    )
    (net (code "41") (name "Net-(L1-Pad2)") (class "Default")
      (node (ref "L1") (pin "2") (pinfunction "2_2") (pintype "passive"))
      (node (ref "L2") (pin "1") (pinfunction "1_1") (pintype "passive"))
      (node (ref "R30") (pin "2") (pinfunction "2_2") (pintype "passive"))
    )
    (net (code "42") (name "Net-(TP5-TP)") (class "Default")
      (node (ref "TP5") (pin "1") (pinfunction "TP_1") (pintype "passive"))
      (node (ref "U1") (pin "2") (pinfunction "MFP0_2") (pintype "passive"))
    )
    (net (code "43") (name "Net-(TP6-TP)") (class "Default")
      (node (ref "TP6") (pin "1") (pinfunction "TP_1") (pintype "passive"))
      (node (ref "U1") (pin "17") (pinfunction "MFP3_17") (pintype "passive"))
    )
    (net (code "44") (name "Net-(TP7-TP)") (class "Default")
      (node (ref "TP7") (pin "1") (pinfunction "TP_1") (pintype "passive"))
      (node (ref "U1") (pin "18") (pinfunction "MFP4_18") (pintype "passive"))
    )
    (net (code "45") (name "Net-(TP8-TP)") (class "Default")
      (node (ref "TP8") (pin "1") (pinfunction "TP_1") (pintype "passive"))
      (node (ref "U1") (pin "21") (pinfunction "MFP5_21") (pintype "passive"))
    )
    (net (code "46") (name "Net-(TP9-TP)") (class "Default")
      (node (ref "TP9") (pin "1") (pinfunction "TP_1") (pintype "passive"))
      (node (ref "U1") (pin "22") (pinfunction "MFP6_22") (pintype "passive"))
    )
    (net (code "47") (name "Net-(TP10-TP)") (class "Default")
      (node (ref "TP10") (pin "1") (pinfunction "TP_1") (pintype "passive"))
      (node (ref "U1") (pin "31") (pinfunction "MFP7_31") (pintype "passive"))
    )
    (net (code "48") (name "Net-(TP11-TP)") (class "Default")
      (node (ref "TP11") (pin "1") (pinfunction "TP_1") (pintype "passive"))
      (node (ref "U1") (pin "32") (pinfunction "MFP8_32") (pintype "passive"))
    )
    (net (code "49") (name "Net-(TP12-TP)") (class "Default")
      (node (ref "TP12") (pin "1") (pinfunction "TP_1") (pintype "passive"))
      (node (ref "U1") (pin "7") (pinfunction "VREF_7") (pintype "power_in"))
    )
    (net (code "50") (name "Net-(U1A-XRES)") (class "Default")
      (node (ref "R22") (pin "2") (pinfunction "2_2") (pintype "passive"))
      (node (ref "U1") (pin "10") (pinfunction "XRES_10") (pintype "passive"))
    )
    (net (code "51") (name "Net-(U1B-PWDNB)") (class "Default")
      (node (ref "R23") (pin "1") (pinfunction "1_1") (pintype "passive"))
      (node (ref "R24") (pin "1") (pinfunction "1_1") (pintype "passive"))
      (node (ref "U1") (pin "1") (pinfunction "PWDNB_1") (pintype "passive"))
    )
    (net (code "52") (name "Net-(U1C-CAP_VDD)") (class "Default")
      (node (ref "C23") (pin "1") (pinfunction "1_1") (pintype "passive"))
      (node (ref "C24") (pin "1") (pinfunction "1_1") (pintype "passive"))
      (node (ref "C25") (pin "2") (pinfunction "2_2") (pintype "passive"))
      (node (ref "U1") (pin "14") (pinfunction "CAP_VDD_14") (pintype "power_in"))
    )
    (net (code "53") (name "Net-(U1C-VDD)") (class "Default")
      (node (ref "C21") (pin "2") (pinfunction "2_2") (pintype "passive"))
      (node (ref "C22") (pin "2") (pinfunction "2_2") (pintype "passive"))
      (node (ref "R29") (pin "2") (pinfunction "2_2") (pintype "passive"))
      (node (ref "U1") (pin "15") (pinfunction "VDD_15") (pintype "power_in"))
    )
    (net (code "54") (name "Net-(U1C-VDD18)") (class "Default")
      (node (ref "C19") (pin "2") (pinfunction "2_2") (pintype "passive"))
      (node (ref "C20") (pin "2") (pinfunction "2_2") (pintype "passive"))
      (node (ref "R28") (pin "2") (pinfunction "2_2") (pintype "passive"))
      (node (ref "U1") (pin "11") (pinfunction "VDD18_11") (pintype "power_in"))
    )
    (net (code "55") (name "Net-(U1C-VDDIO)") (class "Default")
      (node (ref "C17") (pin "1") (pinfunction "1_1") (pintype "passive"))
      (node (ref "C18") (pin "2") (pinfunction "2_2") (pintype "passive"))
      (node (ref "R27") (pin "2") (pinfunction "2_2") (pintype "passive"))
      (node (ref "U1") (pin "16") (pinfunction "VDDIO_16") (pintype "power_in"))
    )
    (net (code "56") (name "unconnected-(D1-IO2-Pad2)") (class "Default")
      (node (ref "D1") (pin "2") (pinfunction "IO2_2") (pintype "bidirectional"))
    )
    (net (code "57") (name "unconnected-(D1-IO3-Pad4)") (class "Default")
      (node (ref "D1") (pin "4") (pinfunction "IO3_4") (pintype "bidirectional"))
    )
    (net (code "58") (name "unconnected-(D1-IO4-Pad5)") (class "Default")
      (node (ref "D1") (pin "5") (pinfunction "IO4_5") (pintype "bidirectional"))
    )
    (net (code "59") (name "unconnected-(D1-NC-Pad6)") (class "Default")
      (node (ref "D1") (pin "6") (pinfunction "NC_6") (pintype "passive"))
    )
    (net (code "60") (name "unconnected-(D1-NC-Pad7)") (class "Default")
      (node (ref "D1") (pin "7") (pinfunction "NC_7") (pintype "passive"))
    )
    (net (code "61") (name "unconnected-(D1-NC-Pad9)") (class "Default")
      (node (ref "D1") (pin "9") (pinfunction "NC_9") (pintype "passive"))
    )
  )
)
